# uC.net
KiCad netlist of a schematic drawn in EAGLE
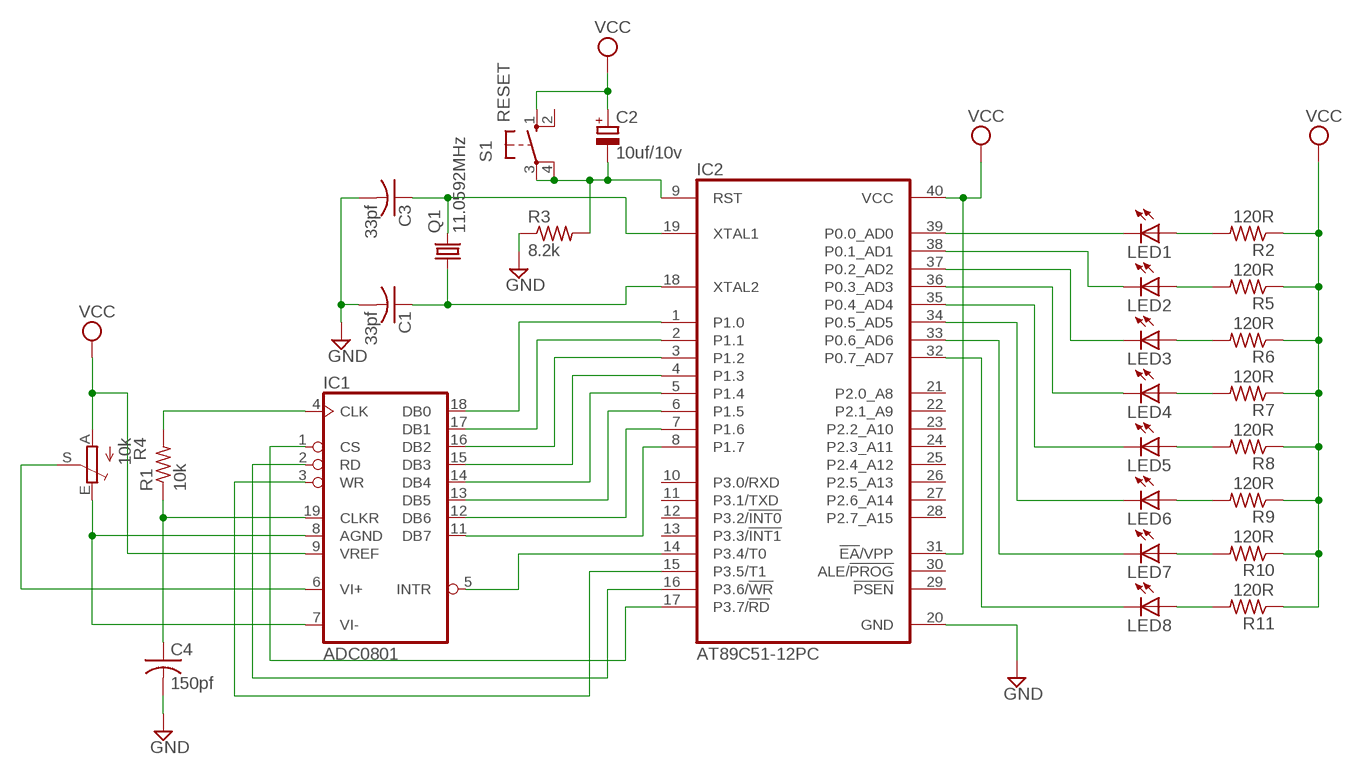
[diagram p0: schematic, sheet 1]

(export (version "E")
  (design (tool "Eeschema 10.0.6"))
  (components
    (comp (ref "C1")
      (value "33pf")
      (footprint "eagle-import:C025-025X050")
      (libsource (lib "eagle-import") (part "C-US025-025X050"))
    )
    (comp (ref "C2")
      (value "10uf/10v")
      (footprint "eagle-import:E2,5-5")
      (libsource (lib "eagle-import") (part "CPOL-EUE2.5-5"))
    )
    (comp (ref "C3")
      (value "33pf")
      (footprint "eagle-import:C025-025X050")
      (libsource (lib "eagle-import") (part "C-US025-025X050"))
    )
    (comp (ref "C4")
      (value "150pf")
      (footprint "eagle-import:C025-025X050")
      (libsource (lib "eagle-import") (part "C-US025-025X050"))
    )
    (comp (ref "IC1")
      (value "ADC0801")
      (footprint "eagle-import:DIL20")
      (libsource (lib "eagle-import") (part "ADC0801"))
    )
    (comp (ref "IC2")
      (value "AT89C51-12PC")
      (footprint "eagle-import:DIL40")
      (libsource (lib "eagle-import") (part "AT89C51-PC12"))
    )
    (comp (ref "LED1")
      (value "LEDCHIPLED_0805")
      (footprint "eagle-import:CHIPLED_0805")
      (libsource (lib "eagle-import") (part "LEDCHIPLED_0805"))
    )
    (comp (ref "LED2")
      (value "LEDCHIPLED_0805")
      (footprint "eagle-import:CHIPLED_0805")
      (libsource (lib "eagle-import") (part "LEDCHIPLED_0805"))
    )
    (comp (ref "LED3")
      (value "LEDCHIPLED_0805")
      (footprint "eagle-import:CHIPLED_0805")
      (libsource (lib "eagle-import") (part "LEDCHIPLED_0805"))
    )
    (comp (ref "LED4")
      (value "LEDCHIPLED_0805")
      (footprint "eagle-import:CHIPLED_0805")
      (libsource (lib "eagle-import") (part "LEDCHIPLED_0805"))
    )
    (comp (ref "LED5")
      (value "LEDCHIPLED_0805")
      (footprint "eagle-import:CHIPLED_0805")
      (libsource (lib "eagle-import") (part "LEDCHIPLED_0805"))
    )
    (comp (ref "LED6")
      (value "LEDCHIPLED_0805")
      (footprint "eagle-import:CHIPLED_0805")
      (libsource (lib "eagle-import") (part "LEDCHIPLED_0805"))
    )
    (comp (ref "LED7")
      (value "LEDCHIPLED_0805")
      (footprint "eagle-import:CHIPLED_0805")
      (libsource (lib "eagle-import") (part "LEDCHIPLED_0805"))
    )
    (comp (ref "LED8")
      (value "LEDCHIPLED_0805")
      (footprint "eagle-import:CHIPLED_0805")
      (libsource (lib "eagle-import") (part "LEDCHIPLED_0805"))
    )
    (comp (ref "Q1")
      (value "11.0592MHz")
      (footprint "eagle-import:TC26H")
      (libsource (lib "eagle-import") (part "CRYSTALTC26H"))
    )
    (comp (ref "R1")
      (value "10k")
      (footprint "eagle-import:R2512")
      (libsource (lib "eagle-import") (part "R-US_R2512"))
    )
    (comp (ref "R2")
      (value "120R")
      (footprint "eagle-import:R2512")
      (libsource (lib "eagle-import") (part "R-US_R2512"))
    )
    (comp (ref "R3")
      (value "8.2k")
      (footprint "eagle-import:R2512")
      (libsource (lib "eagle-import") (part "R-US_R2512"))
    )
    (comp (ref "R4")
      (value "10k")
      (footprint "eagle-import:B25U")
      (libsource (lib "eagle-import") (part "TRIM_EU-B25U"))
    )
    (comp (ref "R5")
      (value "120R")
      (footprint "eagle-import:R2512")
      (libsource (lib "eagle-import") (part "R-US_R2512"))
    )
    (comp (ref "R6")
      (value "120R")
      (footprint "eagle-import:R2512")
      (libsource (lib "eagle-import") (part "R-US_R2512"))
    )
    (comp (ref "R7")
      (value "120R")
      (footprint "eagle-import:R2512")
      (libsource (lib "eagle-import") (part "R-US_R2512"))
    )
    (comp (ref "R8")
      (value "120R")
      (footprint "eagle-import:R2512")
      (libsource (lib "eagle-import") (part "R-US_R2512"))
    )
    (comp (ref "R9")
      (value "120R")
      (footprint "eagle-import:R2512")
      (libsource (lib "eagle-import") (part "R-US_R2512"))
    )
    (comp (ref "R10")
      (value "120R")
      (footprint "eagle-import:R2512")
      (libsource (lib "eagle-import") (part "R-US_R2512"))
    )
    (comp (ref "R11")
      (value "120R")
      (footprint "eagle-import:R2512")
      (libsource (lib "eagle-import") (part "R-US_R2512"))
    )
    (comp (ref "S1")
      (value "RESET")
      (footprint "eagle-import:B3F-10XX")
      (fields (field (name "MPN") "B3F-1000"))
      (libsource (lib "eagle-import") (part "10-XX"))
    )
  )
  (nets
    (net (code "1") (name "GND") (class "Default")
      (node (ref "C1") (pin "2") (pinfunction "2_2") (pintype "passive"))
      (node (ref "C3") (pin "2") (pinfunction "2_2") (pintype "passive"))
      (node (ref "C4") (pin "2") (pinfunction "2_2") (pintype "passive"))
      (node (ref "IC2") (pin "20") (pinfunction "GND_20") (pintype "power_in"))
      (node (ref "R3") (pin "1") (pinfunction "1_1") (pintype "passive"))
    )
    (net (code "2") (name "Net-(IC1A-AGND)") (class "Default")
      (node (ref "IC1") (pin "7") (pinfunction "VI-_7") (pintype "input"))
      (node (ref "IC1") (pin "8") (pinfunction "AGND_8") (pintype "input"))
      (node (ref "R4") (pin "E") (pinfunction "E_E") (pintype "passive"))
    )
    (net (code "3") (name "Net-(IC1A-CLK)") (class "Default")
      (node (ref "IC1") (pin "4") (pinfunction "CLK_4") (pintype "input"))
      (node (ref "R1") (pin "2") (pinfunction "2_2") (pintype "passive"))
    )
    (net (code "4") (name "Net-(IC1A-CLKR)") (class "Default")
      (node (ref "C4") (pin "1") (pinfunction "1_1") (pintype "passive"))
      (node (ref "IC1") (pin "19") (pinfunction "CLKR_19") (pintype "input"))
      (node (ref "R1") (pin "1") (pinfunction "1_1") (pintype "passive"))
    )
    (net (code "5") (name "Net-(IC1A-CS)") (class "Default")
      (node (ref "IC1") (pin "1") (pinfunction "CS_1") (pintype "input"))
      (node (ref "IC2") (pin "17") (pinfunction "P3.7/~{RD}_17") (pintype "bidirectional"))
    )
    (net (code "6") (name "Net-(IC1A-DB0)") (class "Default")
      (node (ref "IC1") (pin "18") (pinfunction "DB0_18") (pintype "output"))
      (node (ref "IC2") (pin "1") (pinfunction "P1.0_1") (pintype "bidirectional"))
    )
    (net (code "7") (name "Net-(IC1A-DB1)") (class "Default")
      (node (ref "IC1") (pin "17") (pinfunction "DB1_17") (pintype "output"))
      (node (ref "IC2") (pin "2") (pinfunction "P1.1_2") (pintype "bidirectional"))
    )
    (net (code "8") (name "Net-(IC1A-DB2)") (class "Default")
      (node (ref "IC1") (pin "16") (pinfunction "DB2_16") (pintype "output"))
      (node (ref "IC2") (pin "3") (pinfunction "P1.2_3") (pintype "bidirectional"))
    )
    (net (code "9") (name "Net-(IC1A-DB3)") (class "Default")
      (node (ref "IC1") (pin "15") (pinfunction "DB3_15") (pintype "output"))
      (node (ref "IC2") (pin "4") (pinfunction "P1.3_4") (pintype "bidirectional"))
    )
    (net (code "10") (name "Net-(IC1A-DB4)") (class "Default")
      (node (ref "IC1") (pin "14") (pinfunction "DB4_14") (pintype "output"))
      (node (ref "IC2") (pin "5") (pinfunction "P1.4_5") (pintype "bidirectional"))
    )
    (net (code "11") (name "Net-(IC1A-DB5)") (class "Default")
      (node (ref "IC1") (pin "13") (pinfunction "DB5_13") (pintype "output"))
      (node (ref "IC2") (pin "6") (pinfunction "P1.5_6") (pintype "bidirectional"))
    )
    (net (code "12") (name "Net-(IC1A-DB6)") (class "Default")
      (node (ref "IC1") (pin "12") (pinfunction "DB6_12") (pintype "output"))
      (node (ref "IC2") (pin "7") (pinfunction "P1.6_7") (pintype "bidirectional"))
    )
    (net (code "13") (name "Net-(IC1A-DB7)") (class "Default")
      (node (ref "IC1") (pin "11") (pinfunction "DB7_11") (pintype "output"))
      (node (ref "IC2") (pin "8") (pinfunction "P1.7_8") (pintype "bidirectional"))
    )
    (net (code "14") (name "Net-(IC1A-INTR)") (class "Default")
      (node (ref "IC1") (pin "5") (pinfunction "INTR_5") (pintype "output"))
      (node (ref "IC2") (pin "14") (pinfunction "P3.4/T0_14") (pintype "bidirectional"))
    )
    (net (code "15") (name "Net-(IC1A-RD)") (class "Default")
      (node (ref "IC1") (pin "2") (pinfunction "RD_2") (pintype "input"))
      (node (ref "IC2") (pin "16") (pinfunction "P3.6/~{WR}_16") (pintype "bidirectional"))
    )
    (net (code "16") (name "Net-(IC1A-VI+)") (class "Default")
      (node (ref "IC1") (pin "6") (pinfunction "VI+_6") (pintype "input"))
      (node (ref "R4") (pin "S") (pinfunction "S_S") (pintype "passive"))
    )
    (net (code "17") (name "Net-(IC1A-WR)") (class "Default")
      (node (ref "IC1") (pin "3") (pinfunction "WR_3") (pintype "input"))
      (node (ref "IC2") (pin "15") (pinfunction "P3.5/T1_15") (pintype "bidirectional"))
    )
    (net (code "18") (name "Net-(IC2-P0.0_AD0)") (class "Default")
      (node (ref "IC2") (pin "39") (pinfunction "P0.0_AD0_39") (pintype "bidirectional"))
      (node (ref "LED1") (pin "C") (pinfunction "C_C") (pintype "passive"))
    )
    (net (code "19") (name "Net-(IC2-P0.1_AD1)") (class "Default")
      (node (ref "IC2") (pin "38") (pinfunction "P0.1_AD1_38") (pintype "bidirectional"))
      (node (ref "LED2") (pin "C") (pinfunction "C_C") (pintype "passive"))
    )
    (net (code "20") (name "Net-(IC2-P0.2_AD2)") (class "Default")
      (node (ref "IC2") (pin "37") (pinfunction "P0.2_AD2_37") (pintype "bidirectional"))
      (node (ref "LED3") (pin "C") (pinfunction "C_C") (pintype "passive"))
    )
    (net (code "21") (name "Net-(IC2-P0.3_AD3)") (class "Default")
      (node (ref "IC2") (pin "36") (pinfunction "P0.3_AD3_36") (pintype "bidirectional"))
      (node (ref "LED4") (pin "C") (pinfunction "C_C") (pintype "passive"))
    )
    (net (code "22") (name "Net-(IC2-P0.4_AD4)") (class "Default")
      (node (ref "IC2") (pin "35") (pinfunction "P0.4_AD4_35") (pintype "bidirectional"))
      (node (ref "LED5") (pin "C") (pinfunction "C_C") (pintype "passive"))
    )
    (net (code "23") (name "Net-(IC2-P0.5_AD5)") (class "Default")
      (node (ref "IC2") (pin "34") (pinfunction "P0.5_AD5_34") (pintype "bidirectional"))
      (node (ref "LED6") (pin "C") (pinfunction "C_C") (pintype "passive"))
    )
    (net (code "24") (name "Net-(IC2-P0.6_AD6)") (class "Default")
      (node (ref "IC2") (pin "33") (pinfunction "P0.6_AD6_33") (pintype "bidirectional"))
      (node (ref "LED7") (pin "C") (pinfunction "C_C") (pintype "passive"))
    )
    (net (code "25") (name "Net-(IC2-P0.7_AD7)") (class "Default")
      (node (ref "IC2") (pin "32") (pinfunction "P0.7_AD7_32") (pintype "bidirectional"))
      (node (ref "LED8") (pin "C") (pinfunction "C_C") (pintype "passive"))
    )
    (net (code "26") (name "Net-(IC2-RST)") (class "Default")
      (node (ref "C2") (pin "-") (pinfunction "-_-") (pintype "passive"))
      (node (ref "IC2") (pin "9") (pinfunction "RST_9") (pintype "input"))
      (node (ref "R3") (pin "2") (pinfunction "2_2") (pintype "passive"))
      (node (ref "S1") (pin "3") (pinfunction "P_3") (pintype "passive"))
      (node (ref "S1") (pin "4") (pinfunction "P1_4") (pintype "passive"))
    )
    (net (code "27") (name "Net-(IC2-XTAL1)") (class "Default")
      (node (ref "C3") (pin "1") (pinfunction "1_1") (pintype "passive"))
      (node (ref "IC2") (pin "19") (pinfunction "XTAL1_19") (pintype "input"))
      (node (ref "Q1") (pin "2") (pinfunction "2_2") (pintype "passive"))
    )
    (net (code "28") (name "Net-(IC2-XTAL2)") (class "Default")
      (node (ref "C1") (pin "1") (pinfunction "1_1") (pintype "passive"))
      (node (ref "IC2") (pin "18") (pinfunction "XTAL2_18") (pintype "input"))
      (node (ref "Q1") (pin "1") (pinfunction "1_1") (pintype "passive"))
    )
    (net (code "29") (name "Net-(LED1-PadA)") (class "Default")
      (node (ref "LED1") (pin "A") (pinfunction "A_A") (pintype "passive"))
      (node (ref "R2") (pin "2") (pinfunction "2_2") (pintype "passive"))
    )
    (net (code "30") (name "Net-(LED2-PadA)") (class "Default")
      (node (ref "LED2") (pin "A") (pinfunction "A_A") (pintype "passive"))
      (node (ref "R5") (pin "2") (pinfunction "2_2") (pintype "passive"))
    )
    (net (code "31") (name "Net-(LED3-PadA)") (class "Default")
      (node (ref "LED3") (pin "A") (pinfunction "A_A") (pintype "passive"))
      (node (ref "R6") (pin "2") (pinfunction "2_2") (pintype "passive"))
    )
    (net (code "32") (name "Net-(LED4-PadA)") (class "Default")
      (node (ref "LED4") (pin "A") (pinfunction "A_A") (pintype "passive"))
      (node (ref "R7") (pin "2") (pinfunction "2_2") (pintype "passive"))
    )
    (net (code "33") (name "Net-(LED5-PadA)") (class "Default")
      (node (ref "LED5") (pin "A") (pinfunction "A_A") (pintype "passive"))
      (node (ref "R8") (pin "2") (pinfunction "2_2") (pintype "passive"))
    )
    (net (code "34") (name "Net-(LED6-PadA)") (class "Default")
      (node (ref "LED6") (pin "A") (pinfunction "A_A") (pintype "passive"))
      (node (ref "R9") (pin "2") (pinfunction "2_2") (pintype "passive"))
    )
    (net (code "35") (name "Net-(LED7-PadA)") (class "Default")
      (node (ref "LED7") (pin "A") (pinfunction "A_A") (pintype "passive"))
      (node (ref "R10") (pin "2") (pinfunction "2_2") (pintype "passive"))
    )
    (net (code "36") (name "Net-(LED8-PadA)") (class "Default")
      (node (ref "LED8") (pin "A") (pinfunction "A_A") (pintype "passive"))
      (node (ref "R11") (pin "2") (pinfunction "2_2") (pintype "passive"))
    )
    (net (code "37") (name "VCC") (class "Default")
      (node (ref "C2") (pin "+") (pinfunction "+_+") (pintype "passive"))
      (node (ref "IC1") (pin "9") (pinfunction "VREF_9") (pintype "input"))
      (node (ref "IC2") (pin "31") (pinfunction "~{EA}/VPP_31") (pintype "input"))
      (node (ref "IC2") (pin "40") (pinfunction "VCC_40") (pintype "power_in"))
      (node (ref "R10") (pin "1") (pinfunction "1_1") (pintype "passive"))
      (node (ref "R11") (pin "1") (pinfunction "1_1") (pintype "passive"))
      (node (ref "R2") (pin "1") (pinfunction "1_1") (pintype "passive"))
      (node (ref "R4") (pin "A") (pinfunction "A_A") (pintype "passive"))
      (node (ref "R5") (pin "1") (pinfunction "1_1") (pintype "passive"))
      (node (ref "R6") (pin "1") (pinfunction "1_1") (pintype "passive"))
      (node (ref "R7") (pin "1") (pinfunction "1_1") (pintype "passive"))
      (node (ref "R8") (pin "1") (pinfunction "1_1") (pintype "passive"))
      (node (ref "R9") (pin "1") (pinfunction "1_1") (pintype "passive"))
      (node (ref "S1") (pin "1") (pinfunction "S_1") (pintype "passive"))
    )
    (net (code "38") (name "unconnected-(IC2-ALE{slash}~{PROG}-Pad30)") (class "Default")
      (node (ref "IC2") (pin "30") (pinfunction "ALE/~{PROG}_30") (pintype "output"))
    )
    (net (code "39") (name "unconnected-(IC2-P2.0_A8-Pad21)") (class "Default")
      (node (ref "IC2") (pin "21") (pinfunction "P2.0_A8_21") (pintype "bidirectional"))
    )
    (net (code "40") (name "unconnected-(IC2-P2.1_A9-Pad22)") (class "Default")
      (node (ref "IC2") (pin "22") (pinfunction "P2.1_A9_22") (pintype "bidirectional"))
    )
    (net (code "41") (name "unconnected-(IC2-P2.2_A10-Pad23)") (class "Default")
      (node (ref "IC2") (pin "23") (pinfunction "P2.2_A10_23") (pintype "bidirectional"))
    )
    (net (code "42") (name "unconnected-(IC2-P2.3_A11-Pad24)") (class "Default")
      (node (ref "IC2") (pin "24") (pinfunction "P2.3_A11_24") (pintype "bidirectional"))
    )
    (net (code "43") (name "unconnected-(IC2-P2.4_A12-Pad25)") (class "Default")
      (node (ref "IC2") (pin "25") (pinfunction "P2.4_A12_25") (pintype "bidirectional"))
    )
    (net (code "44") (name "unconnected-(IC2-P2.5_A13-Pad26)") (class "Default")
      (node (ref "IC2") (pin "26") (pinfunction "P2.5_A13_26") (pintype "bidirectional"))
    )
    (net (code "45") (name "unconnected-(IC2-P2.6_A14-Pad27)") (class "Default")
      (node (ref "IC2") (pin "27") (pinfunction "P2.6_A14_27") (pintype "bidirectional"))
    )
    (net (code "46") (name "unconnected-(IC2-P2.7_A15-Pad28)") (class "Default")
      (node (ref "IC2") (pin "28") (pinfunction "P2.7_A15_28") (pintype "bidirectional"))
    )
    (net (code "47") (name "unconnected-(IC2-P3.0{slash}RXD-Pad10)") (class "Default")
      (node (ref "IC2") (pin "10") (pinfunction "P3.0/RXD_10") (pintype "bidirectional"))
    )
    (net (code "48") (name "unconnected-(IC2-P3.1{slash}TXD-Pad11)") (class "Default")
      (node (ref "IC2") (pin "11") (pinfunction "P3.1/TXD_11") (pintype "bidirectional"))
    )
    (net (code "49") (name "unconnected-(IC2-P3.2{slash}~{INT0}-Pad12)") (class "Default")
      (node (ref "IC2") (pin "12") (pinfunction "P3.2/~{INT0}_12") (pintype "bidirectional"))
    )
    (net (code "50") (name "unconnected-(IC2-P3.3{slash}~{INT1}-Pad13)") (class "Default")
      (node (ref "IC2") (pin "13") (pinfunction "P3.3/~{INT1}_13") (pintype "bidirectional"))
    )
    (net (code "51") (name "unconnected-(IC2-~{PSEN}-Pad29)") (class "Default")
      (node (ref "IC2") (pin "29") (pinfunction "~{PSEN}_29") (pintype "output"))
    )
    (net (code "52") (name "unconnected-(S1-S1-Pad2)") (class "Default")
      (node (ref "S1") (pin "2") (pinfunction "S1_2") (pintype "passive"))
    )
  )
)
